# Sheet1.net
KiCad netlist of a schematic drawn in Altium Designer
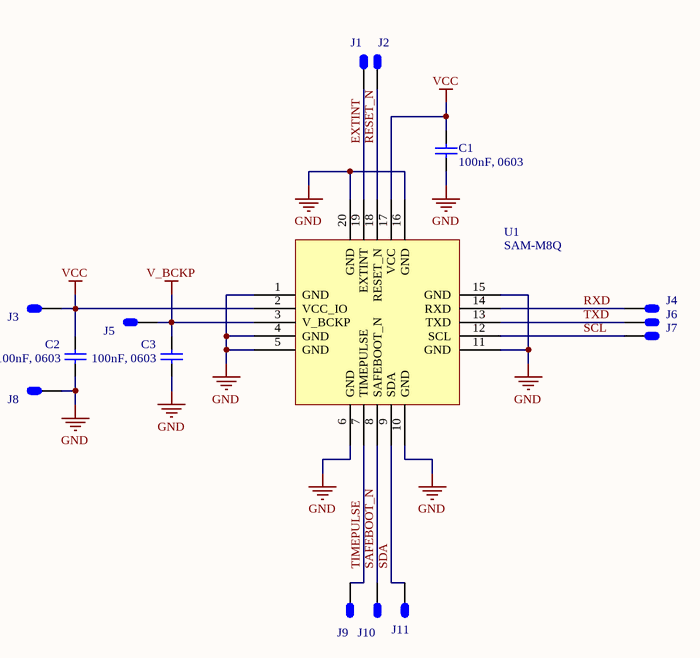
[diagram p0: Sheet1.SchDoc]

(export (version "E")
  (design (tool "Eeschema 10.0.6"))
  (components
    (comp (ref "C1")
      (value "100nF, 0603")
      (footprint "Capacitor 0603")
      (libsource (lib "x-io") (part "Capacitor"))
    )
    (comp (ref "C2")
      (value "100nF, 0603")
      (footprint "Capacitor 0603")
      (libsource (lib "x-io") (part "Capacitor"))
    )
    (comp (ref "C3")
      (value "100nF, 0603")
      (footprint "Capacitor 0603")
      (libsource (lib "x-io") (part "Capacitor"))
    )
    (comp (ref "J1")
      (value "Wire To Board Solder Pad")
      (footprint "Wire To Board Solder Pad")
      (libsource (lib "x-io") (part "Wire To Board Solder Pad"))
    )
    (comp (ref "J2")
      (value "Wire To Board Solder Pad")
      (footprint "Wire To Board Solder Pad")
      (libsource (lib "x-io") (part "Wire To Board Solder Pad"))
    )
    (comp (ref "J3")
      (value "Wire To Board Solder Pad")
      (footprint "Wire To Board Solder Pad")
      (libsource (lib "x-io") (part "Wire To Board Solder Pad"))
    )
    (comp (ref "J4")
      (value "Wire To Board Solder Pad")
      (footprint "Wire To Board Solder Pad")
      (libsource (lib "x-io") (part "Wire To Board Solder Pad"))
    )
    (comp (ref "J5")
      (value "Wire To Board Solder Pad")
      (footprint "Wire To Board Solder Pad")
      (libsource (lib "x-io") (part "Wire To Board Solder Pad"))
    )
    (comp (ref "J6")
      (value "Wire To Board Solder Pad")
      (footprint "Wire To Board Solder Pad")
      (libsource (lib "x-io") (part "Wire To Board Solder Pad"))
    )
    (comp (ref "J7")
      (value "Wire To Board Solder Pad")
      (footprint "Wire To Board Solder Pad")
      (libsource (lib "x-io") (part "Wire To Board Solder Pad"))
    )
    (comp (ref "J8")
      (value "Wire To Board Solder Pad")
      (footprint "Wire To Board Solder Pad")
      (libsource (lib "x-io") (part "Wire To Board Solder Pad"))
    )
    (comp (ref "J9")
      (value "Wire To Board Solder Pad")
      (footprint "Wire To Board Solder Pad")
      (libsource (lib "x-io") (part "Wire To Board Solder Pad"))
    )
    (comp (ref "J10")
      (value "Wire To Board Solder Pad")
      (footprint "Wire To Board Solder Pad")
      (libsource (lib "x-io") (part "Wire To Board Solder Pad"))
    )
    (comp (ref "J11")
      (value "Wire To Board Solder Pad")
      (footprint "Wire To Board Solder Pad")
      (libsource (lib "x-io") (part "Wire To Board Solder Pad"))
    )
    (comp (ref "U1") (value "SAM-M8Q") (footprint "SAM-M8Q") (libsource (lib "x-io") (part "SAM-M8Q")))
  )
  (nets
    (net (code "1") (name "/EXTINT") (class "Default")
      (node (ref "J1") (pin "1") (pinfunction "1_1") (pintype "passive"))
      (node (ref "U1") (pin "19") (pinfunction "EXTINT_19") (pintype "passive"))
    )
    (net (code "2") (name "/RESET_N") (class "Default")
      (node (ref "J2") (pin "1") (pinfunction "1_1") (pintype "passive"))
      (node (ref "U1") (pin "18") (pinfunction "RESET_N_18") (pintype "passive"))
    )
    (net (code "3") (name "/RXD") (class "Default")
      (node (ref "J4") (pin "1") (pinfunction "1_1") (pintype "passive"))
      (node (ref "U1") (pin "14") (pinfunction "RXD_14") (pintype "passive"))
    )
    (net (code "4") (name "/SAFEBOOT_N") (class "Default")
      (node (ref "J10") (pin "1") (pinfunction "1_1") (pintype "passive"))
      (node (ref "U1") (pin "8") (pinfunction "SAFEBOOT_N_8") (pintype "passive"))
    )
    (net (code "5") (name "/SCL") (class "Default")
      (node (ref "J7") (pin "1") (pinfunction "1_1") (pintype "passive"))
      (node (ref "U1") (pin "12") (pinfunction "SCL_12") (pintype "passive"))
    )
    (net (code "6") (name "/SDA") (class "Default")
      (node (ref "J11") (pin "1") (pinfunction "1_1") (pintype "passive"))
      (node (ref "U1") (pin "9") (pinfunction "SDA_9") (pintype "passive"))
    )
    (net (code "7") (name "/TIMEPULSE") (class "Default")
      (node (ref "J9") (pin "1") (pinfunction "1_1") (pintype "passive"))
      (node (ref "U1") (pin "7") (pinfunction "TIMEPULSE_7") (pintype "passive"))
    )
    (net (code "8") (name "/TXD") (class "Default")
      (node (ref "J6") (pin "1") (pinfunction "1_1") (pintype "passive"))
      (node (ref "U1") (pin "13") (pinfunction "TXD_13") (pintype "passive"))
    )
    (net (code "9") (name "GND") (class "Default")
      (node (ref "C1") (pin "1") (pinfunction "1_1") (pintype "passive"))
      (node (ref "C2") (pin "1") (pinfunction "1_1") (pintype "passive"))
      (node (ref "C3") (pin "1") (pinfunction "1_1") (pintype "passive"))
      (node (ref "J8") (pin "1") (pinfunction "1_1") (pintype "passive"))
      (node (ref "U1") (pin "1") (pinfunction "GND_1") (pintype "passive"))
      (node (ref "U1") (pin "10") (pinfunction "GND_10") (pintype "passive"))
      (node (ref "U1") (pin "11") (pinfunction "GND_11") (pintype "passive"))
      (node (ref "U1") (pin "15") (pinfunction "GND_15") (pintype "passive"))
      (node (ref "U1") (pin "16") (pinfunction "GND_16") (pintype "passive"))
      (node (ref "U1") (pin "20") (pinfunction "GND_20") (pintype "passive"))
      (node (ref "U1") (pin "4") (pinfunction "GND_4") (pintype "passive"))
      (node (ref "U1") (pin "5") (pinfunction "GND_5") (pintype "passive"))
      (node (ref "U1") (pin "6") (pinfunction "GND_6") (pintype "passive"))
    )
    (net (code "10") (name "VCC") (class "Default")
      (node (ref "C1") (pin "2") (pinfunction "2_2") (pintype "passive"))
      (node (ref "C2") (pin "2") (pinfunction "2_2") (pintype "passive"))
      (node (ref "J3") (pin "1") (pinfunction "1_1") (pintype "passive"))
      (node (ref "U1") (pin "17") (pinfunction "VCC_17") (pintype "passive"))
      (node (ref "U1") (pin "2") (pinfunction "VCC_IO_2") (pintype "passive"))
    )
    (net (code "11") (name "V_BCKP") (class "Default")
      (node (ref "C3") (pin "2") (pinfunction "2_2") (pintype "passive"))
      (node (ref "J5") (pin "1") (pinfunction "1_1") (pintype "passive"))
      (node (ref "U1") (pin "3") (pinfunction "V_BCKP_3") (pintype "passive"))
    )
  )
)
